# Ethernet.net
KiCad netlist of a schematic drawn in Altium Designer
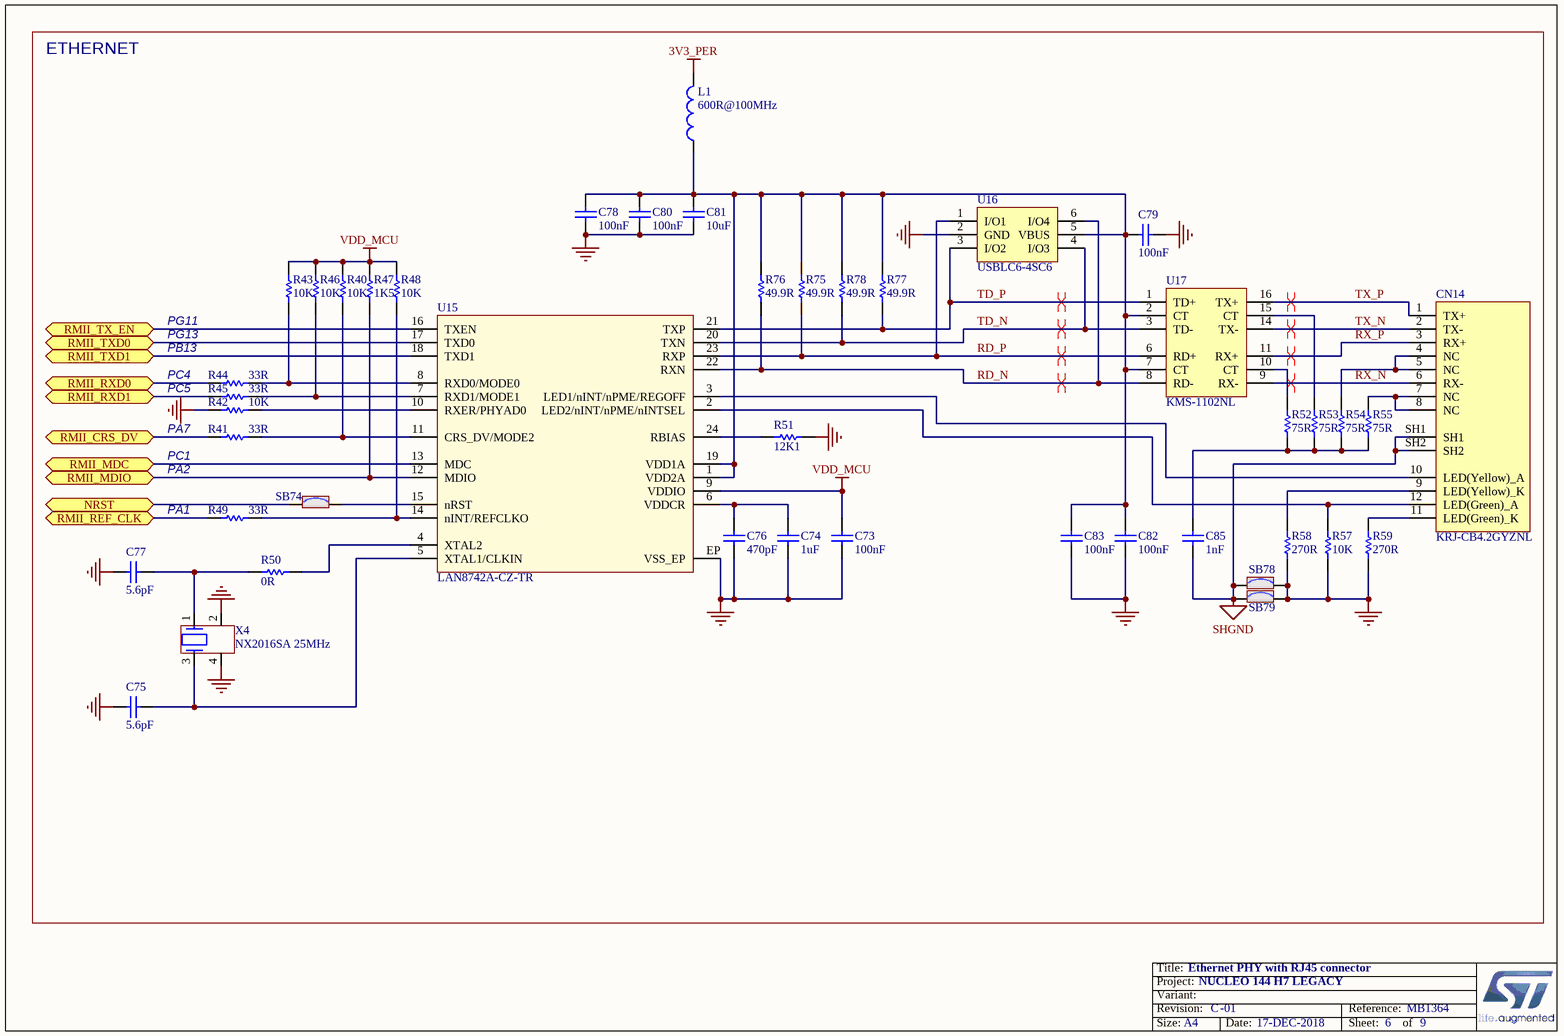
[diagram p0: Ethernet.SchDoc]

(export (version "E")
  (design (tool "Eeschema 10.0.6"))
  (components
    (comp (ref "C73")
      (value "100nF")
      (footprint "C0603")
      (description "Capacitor, MLCC, 100nF, 6V3, X5R, 10%, 0603, T=0,8mm")
      (fields
        (field (name "INTERNAL_PART_NUMBER") "MCD-00237")
        (field (name "MANUFACTURER_PART_NUMBER") "CC0603KRX5R5BB104")
        (field (name "PROVIDED_BY") "SUBCO")
      )
      (libsource (lib "MCD_PARTS_database") (part "Capacitor"))
    )
    (comp (ref "C74")
      (value "1uF")
      (footprint "C0402")
      (description "Capacitor, MLCC, 1uF, 6V3, X5R, 10%, 0402, T=0,5mm")
      (fields
        (field (name "INTERNAL_PART_NUMBER") "MCD-00095")
        (field (name "MANUFACTURER_PART_NUMBER") "GRM155R61E105KA12")
        (field (name "PROVIDED_BY") "SUBCO")
      )
      (libsource (lib "MCD_PARTS_database") (part "Capacitor"))
    )
    (comp (ref "C75")
      (value "5.6pF")
      (footprint "C0402")
      (description "Capacitor, MLCC, 5.6pF, 50V, NPO, 5%, 0402, T=0,5mm")
      (fields
        (field (name "INTERNAL_PART_NUMBER") "MCD-01374")
        (field (name "MANUFACTURER_PART_NUMBER") "CC0402BRNPO9BN5R6")
        (field (name "PROVIDED_BY") "SUBCO")
      )
      (libsource (lib "MCD_PARTS_database") (part "Capacitor"))
    )
    (comp (ref "C76")
      (value "470pF")
      (footprint "C0402")
      (description "Capacitor, MLCC, 470pF, 50V, NPO, 5%, 0402, T=0,5mm")
      (fields
        (field (name "INTERNAL_PART_NUMBER") "MCD-00724")
        (field (name "MANUFACTURER_PART_NUMBER") "CC0402JRNPO9BN471")
        (field (name "PROVIDED_BY") "SUBCO")
      )
      (libsource (lib "MCD_PARTS_database") (part "Capacitor"))
    )
    (comp (ref "C77")
      (value "5.6pF")
      (footprint "C0402")
      (description "Capacitor, MLCC, 5.6pF, 50V, NPO, 5%, 0402, T=0,5mm")
      (fields
        (field (name "INTERNAL_PART_NUMBER") "MCD-01374")
        (field (name "MANUFACTURER_PART_NUMBER") "CC0402BRNPO9BN5R6")
        (field (name "PROVIDED_BY") "SUBCO")
      )
      (libsource (lib "MCD_PARTS_database") (part "Capacitor"))
    )
    (comp (ref "C78")
      (value "100nF")
      (footprint "C0603")
      (description "Capacitor, MLCC, 100nF, 6V3, X5R, 10%, 0603, T=0,8mm")
      (fields
        (field (name "INTERNAL_PART_NUMBER") "MCD-00237")
        (field (name "MANUFACTURER_PART_NUMBER") "CC0603KRX5R5BB104")
        (field (name "PROVIDED_BY") "SUBCO")
      )
      (libsource (lib "MCD_PARTS_database") (part "Capacitor"))
    )
    (comp (ref "C79")
      (value "100nF")
      (footprint "C0603")
      (description "Capacitor, MLCC, 100nF, 6V3, X5R, 10%, 0603, T=0,8mm")
      (fields
        (field (name "INTERNAL_PART_NUMBER") "MCD-00237")
        (field (name "MANUFACTURER_PART_NUMBER") "CC0603KRX5R5BB104")
        (field (name "PROVIDED_BY") "SUBCO")
      )
      (libsource (lib "MCD_PARTS_database") (part "Capacitor"))
    )
    (comp (ref "C80")
      (value "100nF")
      (footprint "C0603")
      (description "Capacitor, MLCC, 100nF, 6V3, X5R, 10%, 0603, T=0,8mm")
      (fields
        (field (name "INTERNAL_PART_NUMBER") "MCD-00237")
        (field (name "MANUFACTURER_PART_NUMBER") "CC0603KRX5R5BB104")
        (field (name "PROVIDED_BY") "SUBCO")
      )
      (libsource (lib "MCD_PARTS_database") (part "Capacitor"))
    )
    (comp (ref "C81")
      (value "10uF")
      (footprint "C0603")
      (description "Capacitor, MLCC, 10µF, 10V, X5R, 10%, 0603, T=0.8mm")
      (fields
        (field (name "INTERNAL_PART_NUMBER") "MCD-01124")
        (field (name "MANUFACTURER_PART_NUMBER") "GRM188R61A106KAAL")
        (field (name "PROVIDED_BY") "SUBCO")
      )
      (libsource (lib "MCD_PARTS_database") (part "Capacitor"))
    )
    (comp (ref "C82")
      (value "100nF")
      (footprint "C0603")
      (description "Capacitor, MLCC, 100nF, 6V3, X5R, 10%, 0603, T=0,8mm")
      (fields
        (field (name "INTERNAL_PART_NUMBER") "MCD-00237")
        (field (name "MANUFACTURER_PART_NUMBER") "CC0603KRX5R5BB104")
        (field (name "PROVIDED_BY") "SUBCO")
      )
      (libsource (lib "MCD_PARTS_database") (part "Capacitor"))
    )
    (comp (ref "C83")
      (value "100nF")
      (footprint "C0603")
      (description "Capacitor, MLCC, 100nF, 6V3, X5R, 10%, 0603, T=0,8mm")
      (fields
        (field (name "INTERNAL_PART_NUMBER") "MCD-00237")
        (field (name "MANUFACTURER_PART_NUMBER") "CC0603KRX5R5BB104")
        (field (name "PROVIDED_BY") "SUBCO")
      )
      (libsource (lib "MCD_PARTS_database") (part "Capacitor"))
    )
    (comp (ref "C85")
      (value "1nF")
      (footprint "C1206_H1P6")
      (description "Capacitor, MLCC, 1nF, 2KV, X7R, 10%, 1206, T=1,25mm")
      (fields
        (field (name "INTERNAL_PART_NUMBER") "MCD-00722")
        (field (name "MANUFACTURER_PART_NUMBER") "CC1206KKX7RDBB102")
        (field (name "PROVIDED_BY") "SUBCO")
      )
      (libsource (lib "MCD_PARTS_database") (part "Capacitor"))
    )
    (comp (ref "CN14")
      (value "KRJ-CB4.2GYZNL")
      (footprint "CON_RJ45_DGKYD_KRJ-CB4.2GYZNL")
      (description "RJ45 jack, single port, with LEDS, Metal shielded dip low profile")
      (fields
        (field (name "INTERNAL_PART_NUMBER") "MCD-00717")
        (field (name "MANUFACTURER") "DONGGUAN KEYOUDA ELECTRONIC TECHNOLOGY")
        (field (name "PROVIDED_BY") "SUBCO")
      )
      (libsource (lib "MCD_PARTS_database") (part "RJ45_KRJ-CB4.2GYZNL"))
    )
    (comp (ref "L1")
      (value "600R@100MHz")
      (footprint "L0603")
      (description "SMD Chip ferrite bead, 600R@100MHz +/-25%, 350mA, 500mohm DC, 0603, T=0.8mm")
      (fields
        (field (name "INTERNAL_PART_NUMBER") "MCD-00047")
        (field (name "MANUFACTURER_PART_NUMBER") "FCM1608KF-601T03")
        (field (name "PROVIDED_BY") "SUBCO")
      )
      (libsource (lib "MCD_PARTS_database") (part "BEAD"))
    )
    (comp (ref "R40")
      (value "10K")
      (footprint "R0402")
      (description "Resistor,10K,0402,1%,1/16W")
      (fields
        (field (name "INTERNAL_PART_NUMBER") "MCD-00053")
        (field (name "MANUFACTURER_PART_NUMBER") "RC0402FR-0710KL")
        (field (name "PROVIDED_BY") "SUBCO")
      )
      (libsource (lib "MCD_PARTS_database") (part "Resistor"))
    )
    (comp (ref "R41")
      (value "33R")
      (footprint "R0402")
      (description "Resistor,33R,0402,1%,1/16W")
      (fields
        (field (name "INTERNAL_PART_NUMBER") "MCD-00455")
        (field (name "MANUFACTURER_PART_NUMBER") "RC0402FR-0733RL")
        (field (name "PROVIDED_BY") "SUBCO")
      )
      (libsource (lib "MCD_PARTS_database") (part "Resistor"))
    )
    (comp (ref "R42")
      (value "10K")
      (footprint "R0402")
      (description "Resistor,10K,0402,1%,1/16W")
      (fields
        (field (name "INTERNAL_PART_NUMBER") "MCD-00053")
        (field (name "MANUFACTURER_PART_NUMBER") "RC0402FR-0710KL")
        (field (name "PROVIDED_BY") "SUBCO")
      )
      (libsource (lib "MCD_PARTS_database") (part "Resistor"))
    )
    (comp (ref "R43")
      (value "10K")
      (footprint "R0402")
      (description "Resistor,10K,0402,1%,1/16W")
      (fields
        (field (name "INTERNAL_PART_NUMBER") "MCD-00053")
        (field (name "MANUFACTURER_PART_NUMBER") "RC0402FR-0710KL")
        (field (name "PROVIDED_BY") "SUBCO")
      )
      (libsource (lib "MCD_PARTS_database") (part "Resistor"))
    )
    (comp (ref "R44")
      (value "33R")
      (footprint "R0402")
      (description "Resistor,33R,0402,1%,1/16W")
      (fields
        (field (name "INTERNAL_PART_NUMBER") "MCD-00455")
        (field (name "MANUFACTURER_PART_NUMBER") "RC0402FR-0733RL")
        (field (name "PROVIDED_BY") "SUBCO")
      )
      (libsource (lib "MCD_PARTS_database") (part "Resistor"))
    )
    (comp (ref "R45")
      (value "33R")
      (footprint "R0402")
      (description "Resistor,33R,0402,1%,1/16W")
      (fields
        (field (name "INTERNAL_PART_NUMBER") "MCD-00455")
        (field (name "MANUFACTURER_PART_NUMBER") "RC0402FR-0733RL")
        (field (name "PROVIDED_BY") "SUBCO")
      )
      (libsource (lib "MCD_PARTS_database") (part "Resistor"))
    )
    (comp (ref "R46")
      (value "10K")
      (footprint "R0402")
      (description "Resistor,10K,0402,1%,1/16W")
      (fields
        (field (name "INTERNAL_PART_NUMBER") "MCD-00053")
        (field (name "MANUFACTURER_PART_NUMBER") "RC0402FR-0710KL")
        (field (name "PROVIDED_BY") "SUBCO")
      )
      (libsource (lib "MCD_PARTS_database") (part "Resistor"))
    )
    (comp (ref "R47")
      (value "1K5")
      (footprint "R0402")
      (description "Resistor,1K5,0402,1%,1/16W")
      (fields
        (field (name "INTERNAL_PART_NUMBER") "MCD-00068")
        (field (name "MANUFACTURER_PART_NUMBER") "RC0402FR-071K5L")
        (field (name "PROVIDED_BY") "SUBCO")
      )
      (libsource (lib "MCD_PARTS_database") (part "Resistor"))
    )
    (comp (ref "R48")
      (value "10K")
      (footprint "R0402")
      (description "Resistor,10K,0402,1%,1/16W")
      (fields
        (field (name "INTERNAL_PART_NUMBER") "MCD-00053")
        (field (name "MANUFACTURER_PART_NUMBER") "RC0402FR-0710KL")
        (field (name "PROVIDED_BY") "SUBCO")
      )
      (libsource (lib "MCD_PARTS_database") (part "Resistor"))
    )
    (comp (ref "R49")
      (value "33R")
      (footprint "R0402")
      (description "Resistor,33R,0402,1%,1/16W")
      (fields
        (field (name "INTERNAL_PART_NUMBER") "MCD-00455")
        (field (name "MANUFACTURER_PART_NUMBER") "RC0402FR-0733RL")
        (field (name "PROVIDED_BY") "SUBCO")
      )
      (libsource (lib "MCD_PARTS_database") (part "Resistor"))
    )
    (comp (ref "R50")
      (value "0R")
      (footprint "R0402")
      (description "Resistor,0R,0402,5%,1/16W")
      (fields
        (field (name "INTERNAL_PART_NUMBER") "MCD-00052")
        (field (name "MANUFACTURER_PART_NUMBER") "RC0402JR-070RL")
        (field (name "PROVIDED_BY") "SUBCO")
      )
      (libsource (lib "MCD_PARTS_database") (part "Resistor"))
    )
    (comp (ref "R51")
      (value "12K1")
      (footprint "R0402")
      (description "Resistor,12K1,0402,1%,1/16W")
      (fields
        (field (name "INTERNAL_PART_NUMBER") "MCD-00723")
        (field (name "MANUFACTURER_PART_NUMBER") "RC0402FR-0712K1L")
        (field (name "PROVIDED_BY") "SUBCO")
      )
      (libsource (lib "MCD_PARTS_database") (part "Resistor"))
    )
    (comp (ref "R52")
      (value "75R")
      (footprint "R0402")
      (description "Resistor,75R,0402,1%,1/16W")
      (fields
        (field (name "INTERNAL_PART_NUMBER") "MCD-00515")
        (field (name "MANUFACTURER_PART_NUMBER") "RC0402FR-0775RL")
        (field (name "PROVIDED_BY") "SUBCO")
      )
      (libsource (lib "MCD_PARTS_database") (part "Resistor"))
    )
    (comp (ref "R53")
      (value "75R")
      (footprint "R0402")
      (description "Resistor,75R,0402,1%,1/16W")
      (fields
        (field (name "INTERNAL_PART_NUMBER") "MCD-00515")
        (field (name "MANUFACTURER_PART_NUMBER") "RC0402FR-0775RL")
        (field (name "PROVIDED_BY") "SUBCO")
      )
      (libsource (lib "MCD_PARTS_database") (part "Resistor"))
    )
    (comp (ref "R54")
      (value "75R")
      (footprint "R0402")
      (description "Resistor,75R,0402,1%,1/16W")
      (fields
        (field (name "INTERNAL_PART_NUMBER") "MCD-00515")
        (field (name "MANUFACTURER_PART_NUMBER") "RC0402FR-0775RL")
        (field (name "PROVIDED_BY") "SUBCO")
      )
      (libsource (lib "MCD_PARTS_database") (part "Resistor"))
    )
    (comp (ref "R55")
      (value "75R")
      (footprint "R0402")
      (description "Resistor,75R,0402,1%,1/16W")
      (fields
        (field (name "INTERNAL_PART_NUMBER") "MCD-00515")
        (field (name "MANUFACTURER_PART_NUMBER") "RC0402FR-0775RL")
        (field (name "PROVIDED_BY") "SUBCO")
      )
      (libsource (lib "MCD_PARTS_database") (part "Resistor"))
    )
    (comp (ref "R57")
      (value "10K")
      (footprint "R0402")
      (description "Resistor,10K,0402,1%,1/16W")
      (fields
        (field (name "INTERNAL_PART_NUMBER") "MCD-00053")
        (field (name "MANUFACTURER_PART_NUMBER") "RC0402FR-0710KL")
        (field (name "PROVIDED_BY") "SUBCO")
      )
      (libsource (lib "MCD_PARTS_database") (part "Resistor"))
    )
    (comp (ref "R58")
      (value "270R")
      (footprint "R0402")
      (description "Resistor,270R,0402,1%,1/16W")
      (fields
        (field (name "INTERNAL_PART_NUMBER") "MCD-00441")
        (field (name "MANUFACTURER_PART_NUMBER") "RC0402FR-07270RL")
        (field (name "PROVIDED_BY") "SUBCO")
      )
      (libsource (lib "MCD_PARTS_database") (part "Resistor"))
    )
    (comp (ref "R59")
      (value "270R")
      (footprint "R0402")
      (description "Resistor,270R,0402,1%,1/16W")
      (fields
        (field (name "INTERNAL_PART_NUMBER") "MCD-00441")
        (field (name "MANUFACTURER_PART_NUMBER") "RC0402FR-07270RL")
        (field (name "PROVIDED_BY") "SUBCO")
      )
      (libsource (lib "MCD_PARTS_database") (part "Resistor"))
    )
    (comp (ref "R75")
      (value "49.9R")
      (footprint "R0402")
      (description "Resistor,49R9,0402,1%,1/16W")
      (fields
        (field (name "INTERNAL_PART_NUMBER") "MCD-00565")
        (field (name "MANUFACTURER_PART_NUMBER") "RC0402FR-0749R9L")
        (field (name "PROVIDED_BY") "SUBCO")
      )
      (libsource (lib "MCD_PARTS_database") (part "Resistor"))
    )
    (comp (ref "R76")
      (value "49.9R")
      (footprint "R0402")
      (description "Resistor,49R9,0402,1%,1/16W")
      (fields
        (field (name "INTERNAL_PART_NUMBER") "MCD-00565")
        (field (name "MANUFACTURER_PART_NUMBER") "RC0402FR-0749R9L")
        (field (name "PROVIDED_BY") "SUBCO")
      )
      (libsource (lib "MCD_PARTS_database") (part "Resistor"))
    )
    (comp (ref "R77")
      (value "49.9R")
      (footprint "R0402")
      (description "Resistor,49R9,0402,1%,1/16W")
      (fields
        (field (name "INTERNAL_PART_NUMBER") "MCD-00565")
        (field (name "MANUFACTURER_PART_NUMBER") "RC0402FR-0749R9L")
        (field (name "PROVIDED_BY") "SUBCO")
      )
      (libsource (lib "MCD_PARTS_database") (part "Resistor"))
    )
    (comp (ref "R78")
      (value "49.9R")
      (footprint "R0402")
      (description "Resistor,49R9,0402,1%,1/16W")
      (fields
        (field (name "INTERNAL_PART_NUMBER") "MCD-00565")
        (field (name "MANUFACTURER_PART_NUMBER") "RC0402FR-0749R9L")
        (field (name "PROVIDED_BY") "SUBCO")
      )
      (libsource (lib "MCD_PARTS_database") (part "Resistor"))
    )
    (comp (ref "SB74")
      (value "SB_ON")
      (footprint "SOLDER-BRIDGE_R0603-0R")
      (description "Solder Bridge ON")
      (fields
        (field (name "INTERNAL_PART_NUMBER") "MCD-00071")
        (field (name "MANUFACTURER_PART_NUMBER") "RC0603JR-070RL")
        (field (name "PROVIDED_BY") "SUBCO")
      )
      (libsource (lib "MCD_PARTS_database") (part "SB_ON"))
    )
    (comp (ref "SB78")
      (value "SB_ON")
      (footprint "SOLDER-BRIDGE_R0603-0R")
      (description "Solder Bridge ON")
      (fields
        (field (name "INTERNAL_PART_NUMBER") "MCD-00071")
        (field (name "MANUFACTURER_PART_NUMBER") "RC0603JR-070RL")
        (field (name "PROVIDED_BY") "SUBCO")
      )
      (libsource (lib "MCD_PARTS_database") (part "SB_ON"))
    )
    (comp (ref "SB79")
      (value "SB_ON")
      (footprint "SOLDER-BRIDGE_R0603-0R")
      (description "Solder Bridge ON")
      (fields
        (field (name "INTERNAL_PART_NUMBER") "MCD-00071")
        (field (name "MANUFACTURER_PART_NUMBER") "RC0603JR-070RL")
        (field (name "PROVIDED_BY") "SUBCO")
      )
      (libsource (lib "MCD_PARTS_database") (part "SB_ON"))
    )
    (comp (ref "U15")
      (value "LAN8742A-CZ-TR")
      (footprint "ICC_VQFN24-EPAD_4X4_P050")
      (description "10/100M RMII Ethernet transceiver")
      (fields
        (field (name "INTERNAL_PART_NUMBER") "MCD-00719")
        (field (name "MANUFACTURER") "MICROCHIP")
        (field (name "PROVIDED_BY") "SUBCO")
      )
      (libsource (lib "MCD_PARTS_database") (part "LAN8742A-CZ-TR"))
    )
    (comp (ref "U16")
      (value "USBLC6-4SC6")
      (footprint "ESD_SOT23-6L")
      (description "Very low capacitance ESD protection , 4 lines")
      (fields
        (field (name "INTERNAL_PART_NUMBER") "MCD-00250")
        (field (name "MANUFACTURER") "STMICROELECTRONICS")
        (field (name "PROVIDED_BY") "SUBCO with ST control")
      )
      (libsource (lib "MCD_PARTS_database") (part "USBLC6-4SC6"))
    )
    (comp (ref "U17")
      (value "KMS-1102NL")
      (footprint "TRS_DGKYD_KMS-1102NL")
      (description "Discrete Magnetic Transformer Module, 16 pins, SMT, 100 Base-TX")
      (fields
        (field (name "INTERNAL_PART_NUMBER") "MCD-00718")
        (field (name "MANUFACTURER") "DONGGUAN KEYOUDA ELECTRONIC TECHNOLOGY")
        (field (name "PROVIDED_BY") "SUBCO")
      )
      (libsource (lib "MCD_PARTS_database") (part "KMS-1102NL"))
    )
    (comp (ref "X4")
      (value "NX2016SA 25MHz")
      (footprint "CRY_NX2016SA_4P")
      (description "Crystal 25MHz, 6pF, +-20ppm, 80ohms max, SMD")
      (fields
        (field (name "INTERNAL_PART_NUMBER") "MCD-01364")
        (field (name "MANUFACTURER_PART_NUMBER") "NX2016SA 25MHz EXS00A-CS11321")
        (field (name "PROVIDED_BY") "SUBCO")
      )
      (libsource (lib "MCD_PARTS_database") (part "XTAL_4_PINS"))
    )
  )
  (nets
    (net (code "1") (name "/NRST") (class "Default")
      (node (ref "SB74") (pin "1") (pinfunction "1_1") (pintype "passive"))
    )
    (net (code "2") (name "/RD_N") (class "Default")
      (node (ref "R76") (pin "1") (pinfunction "1_1") (pintype "passive"))
      (node (ref "U15") (pin "22") (pinfunction "RXN_22") (pintype "passive"))
      (node (ref "U16") (pin "6") (pinfunction "I/O4_6") (pintype "passive"))
      (node (ref "U17") (pin "8") (pinfunction "RD-_8") (pintype "passive"))
    )
    (net (code "3") (name "/RD_P") (class "Default")
      (node (ref "R75") (pin "1") (pinfunction "1_1") (pintype "passive"))
      (node (ref "U15") (pin "23") (pinfunction "RXP_23") (pintype "passive"))
      (node (ref "U16") (pin "1") (pinfunction "I/O1_1") (pintype "passive"))
      (node (ref "U17") (pin "6") (pinfunction "RD+_6") (pintype "passive"))
    )
    (net (code "4") (name "/RMII_CRS_DV") (class "Default")
      (node (ref "R41") (pin "1") (pinfunction "1_1") (pintype "passive"))
    )
    (net (code "5") (name "/RMII_MDC") (class "Default")
      (node (ref "U15") (pin "13") (pinfunction "MDC_13") (pintype "passive"))
    )
    (net (code "6") (name "/RMII_MDIO") (class "Default")
      (node (ref "R47") (pin "1") (pinfunction "1_1") (pintype "passive"))
      (node (ref "U15") (pin "12") (pinfunction "MDIO_12") (pintype "passive"))
    )
    (net (code "7") (name "/RMII_REF_CLK") (class "Default")
      (node (ref "R49") (pin "1") (pinfunction "1_1") (pintype "passive"))
    )
    (net (code "8") (name "/RMII_RXD0") (class "Default")
      (node (ref "R44") (pin "1") (pinfunction "1_1") (pintype "passive"))
    )
    (net (code "9") (name "/RMII_RXD1") (class "Default")
      (node (ref "R45") (pin "1") (pinfunction "1_1") (pintype "passive"))
    )
    (net (code "10") (name "/RMII_TXD0") (class "Default")
      (node (ref "U15") (pin "17") (pinfunction "TXD0_17") (pintype "passive"))
    )
    (net (code "11") (name "/RMII_TXD1") (class "Default")
      (node (ref "U15") (pin "18") (pinfunction "TXD1_18") (pintype "passive"))
    )
    (net (code "12") (name "/RMII_TX_EN") (class "Default")
      (node (ref "U15") (pin "16") (pinfunction "TXEN_16") (pintype "passive"))
    )
    (net (code "13") (name "/RX_N") (class "Default")
      (node (ref "CN14") (pin "6") (pinfunction "RX-_6") (pintype "passive"))
      (node (ref "U17") (pin "9") (pinfunction "RX-_9") (pintype "passive"))
    )
    (net (code "14") (name "/RX_P") (class "Default")
      (node (ref "CN14") (pin "3") (pinfunction "RX+_3") (pintype "passive"))
      (node (ref "U17") (pin "11") (pinfunction "RX+_11") (pintype "passive"))
    )
    (net (code "15") (name "/TD_N") (class "Default")
      (node (ref "R78") (pin "1") (pinfunction "1_1") (pintype "passive"))
      (node (ref "U15") (pin "20") (pinfunction "TXN_20") (pintype "passive"))
      (node (ref "U16") (pin "4") (pinfunction "I/O3_4") (pintype "passive"))
      (node (ref "U17") (pin "3") (pinfunction "TD-_3") (pintype "passive"))
    )
    (net (code "16") (name "/TD_P") (class "Default")
      (node (ref "R77") (pin "1") (pinfunction "1_1") (pintype "passive"))
      (node (ref "U15") (pin "21") (pinfunction "TXP_21") (pintype "passive"))
      (node (ref "U16") (pin "3") (pinfunction "I/O2_3") (pintype "passive"))
      (node (ref "U17") (pin "1") (pinfunction "TD+_1") (pintype "passive"))
    )
    (net (code "17") (name "/TX_N") (class "Default")
      (node (ref "CN14") (pin "2") (pinfunction "TX-_2") (pintype "passive"))
      (node (ref "U17") (pin "14") (pinfunction "TX-_14") (pintype "passive"))
    )
    (net (code "18") (name "/TX_P") (class "Default")
      (node (ref "CN14") (pin "1") (pinfunction "TX+_1") (pintype "passive"))
      (node (ref "U17") (pin "16") (pinfunction "TX+_16") (pintype "passive"))
    )
    (net (code "19") (name "3V3_PER") (class "Default")
      (node (ref "L1") (pin "2") (pinfunction "2_2") (pintype "passive"))
    )
    (net (code "20") (name "GND") (class "Default")
      (node (ref "C73") (pin "1") (pinfunction "1_1") (pintype "passive"))
      (node (ref "C74") (pin "1") (pinfunction "1_1") (pintype "passive"))
      (node (ref "C75") (pin "1") (pinfunction "1_1") (pintype "passive"))
      (node (ref "C76") (pin "1") (pinfunction "1_1") (pintype "passive"))
      (node (ref "C77") (pin "1") (pinfunction "1_1") (pintype "passive"))
      (node (ref "C78") (pin "1") (pinfunction "1_1") (pintype "passive"))
      (node (ref "C79") (pin "2") (pinfunction "2_2") (pintype "passive"))
      (node (ref "C80") (pin "1") (pinfunction "1_1") (pintype "passive"))
      (node (ref "C81") (pin "1") (pinfunction "1_1") (pintype "passive"))
      (node (ref "C82") (pin "1") (pinfunction "1_1") (pintype "passive"))
      (node (ref "C83") (pin "1") (pinfunction "1_1") (pintype "passive"))
      (node (ref "R42") (pin "2") (pinfunction "2_2") (pintype "passive"))
      (node (ref "R51") (pin "2") (pinfunction "2_2") (pintype "passive"))
      (node (ref "R57") (pin "1") (pinfunction "1_1") (pintype "passive"))
      (node (ref "R58") (pin "1") (pinfunction "1_1") (pintype "passive"))
      (node (ref "R59") (pin "1") (pinfunction "1_1") (pintype "passive"))
      (node (ref "SB78") (pin "2") (pinfunction "2_2") (pintype "passive"))
      (node (ref "SB79") (pin "2") (pinfunction "2_2") (pintype "passive"))
      (node (ref "U15") (pin "EP") (pinfunction "VSS_EP_EP") (pintype "passive"))
      (node (ref "U16") (pin "2") (pinfunction "GND_2") (pintype "passive"))
      (node (ref "X4") (pin "2") (pinfunction "2_2") (pintype "passive"))
      (node (ref "X4") (pin "4") (pinfunction "4_4") (pintype "passive"))
    )
    (net (code "21") (name "Net-(C77-Pad2)") (class "Default")
      (node (ref "C77") (pin "2") (pinfunction "2_2") (pintype "passive"))
      (node (ref "R50") (pin "1") (pinfunction "1_1") (pintype "passive"))
      (node (ref "X4") (pin "1") (pinfunction "1_1") (pintype "passive"))
    )
    (net (code "22") (name "Net-(C85-Pad2)") (class "Default")
      (node (ref "C85") (pin "2") (pinfunction "2_2") (pintype "passive"))
      (node (ref "R52") (pin "1") (pinfunction "1_1") (pintype "passive"))
      (node (ref "R53") (pin "1") (pinfunction "1_1") (pintype "passive"))
      (node (ref "R54") (pin "1") (pinfunction "1_1") (pintype "passive"))
      (node (ref "R55") (pin "1") (pinfunction "1_1") (pintype "passive"))
    )
    (net (code "23") (name "Net-(CN14-LED(Green)_A)") (class "Default")
      (node (ref "CN14") (pin "12") (pinfunction "LED(Green)_A_12") (pintype "passive"))
      (node (ref "R57") (pin "2") (pinfunction "2_2") (pintype "passive"))
      (node (ref "U15") (pin "2") (pinfunction "LED2/nINT/nPME/nINTSEL_2") (pintype "passive"))
    )
    (net (code "24") (name "Net-(CN14-LED(Green)_K)") (class "Default")
      (node (ref "CN14") (pin "11") (pinfunction "LED(Green)_K_11") (pintype "passive"))
      (node (ref "R59") (pin "2") (pinfunction "2_2") (pintype "passive"))
    )
    (net (code "25") (name "Net-(CN14-LED(Yellow)_A)") (class "Default")
      (node (ref "CN14") (pin "10") (pinfunction "LED(Yellow)_A_10") (pintype "passive"))
      (node (ref "U15") (pin "3") (pinfunction "LED1/nINT/nPME/REGOFF_3") (pintype "passive"))
    )
    (net (code "26") (name "Net-(CN14-LED(Yellow)_K)") (class "Default")
      (node (ref "CN14") (pin "9") (pinfunction "LED(Yellow)_K_9") (pintype "passive"))
      (node (ref "R58") (pin "2") (pinfunction "2_2") (pintype "passive"))
    )
    (net (code "27") (name "Net-(CN14-NC-Pad4)") (class "Default")
      (node (ref "CN14") (pin "4") (pinfunction "NC_4") (pintype "passive"))
      (node (ref "CN14") (pin "5") (pinfunction "NC_5") (pintype "passive"))
      (node (ref "R54") (pin "2") (pinfunction "2_2") (pintype "passive"))
    )
    (net (code "28") (name "Net-(CN14-NC-Pad7)") (class "Default")
      (node (ref "CN14") (pin "7") (pinfunction "NC_7") (pintype "passive"))
      (node (ref "CN14") (pin "8") (pinfunction "NC_8") (pintype "passive"))
      (node (ref "R55") (pin "2") (pinfunction "2_2") (pintype "passive"))
    )
    (net (code "29") (name "Net-(R52-Pad2)") (class "Default")
      (node (ref "R52") (pin "2") (pinfunction "2_2") (pintype "passive"))
      (node (ref "U17") (pin "10") (pinfunction "CT_10") (pintype "passive"))
    )
    (net (code "30") (name "Net-(R53-Pad2)") (class "Default")
      (node (ref "R53") (pin "2") (pinfunction "2_2") (pintype "passive"))
      (node (ref "U17") (pin "15") (pinfunction "CT_15") (pintype "passive"))
    )
    (net (code "31") (name "Net-(U15-CRS_DV{slash}MODE2)") (class "Default")
      (node (ref "R40") (pin "1") (pinfunction "1_1") (pintype "passive"))
      (node (ref "R41") (pin "2") (pinfunction "2_2") (pintype "passive"))
      (node (ref "U15") (pin "11") (pinfunction "CRS_DV/MODE2_11") (pintype "passive"))
    )
    (net (code "32") (name "Net-(U15-RBIAS)") (class "Default")
      (node (ref "R51") (pin "1") (pinfunction "1_1") (pintype "passive"))
      (node (ref "U15") (pin "24") (pinfunction "RBIAS_24") (pintype "passive"))
    )
    (net (code "33") (name "Net-(U15-RXD0{slash}MODE0)") (class "Default")
      (node (ref "R43") (pin "1") (pinfunction "1_1") (pintype "passive"))
      (node (ref "R44") (pin "2") (pinfunction "2_2") (pintype "passive"))
      (node (ref "U15") (pin "8") (pinfunction "RXD0/MODE0_8") (pintype "passive"))
    )
    (net (code "34") (name "Net-(U15-RXD1{slash}MODE1)") (class "Default")
      (node (ref "R45") (pin "2") (pinfunction "2_2") (pintype "passive"))
      (node (ref "R46") (pin "1") (pinfunction "1_1") (pintype "passive"))
      (node (ref "U15") (pin "7") (pinfunction "RXD1/MODE1_7") (pintype "passive"))
    )
    (net (code "35") (name "Net-(U15-RXER{slash}PHYAD0)") (class "Default")
      (node (ref "R42") (pin "1") (pinfunction "1_1") (pintype "passive"))
      (node (ref "U15") (pin "10") (pinfunction "RXER/PHYAD0_10") (pintype "passive"))
    )
    (net (code "36") (name "Net-(U15-VDD1A)") (class "Default")
      (node (ref "C78") (pin "2") (pinfunction "2_2") (pintype "passive"))
      (node (ref "C79") (pin "1") (pinfunction "1_1") (pintype "passive"))
      (node (ref "C80") (pin "2") (pinfunction "2_2") (pintype "passive"))
      (node (ref "C81") (pin "2") (pinfunction "2_2") (pintype "passive"))
      (node (ref "C82") (pin "2") (pinfunction "2_2") (pintype "passive"))
      (node (ref "C83") (pin "2") (pinfunction "2_2") (pintype "passive"))
      (node (ref "L1") (pin "1") (pinfunction "1_1") (pintype "passive"))
      (node (ref "R75") (pin "2") (pinfunction "2_2") (pintype "passive"))
      (node (ref "R76") (pin "2") (pinfunction "2_2") (pintype "passive"))
      (node (ref "R77") (pin "2") (pinfunction "2_2") (pintype "passive"))
      (node (ref "R78") (pin "2") (pinfunction "2_2") (pintype "passive"))
      (node (ref "U15") (pin "1") (pinfunction "VDD2A_1") (pintype "passive"))
      (node (ref "U15") (pin "19") (pinfunction "VDD1A_19") (pintype "passive"))
      (node (ref "U16") (pin "5") (pinfunction "VBUS_5") (pintype "passive"))
      (node (ref "U17") (pin "2") (pinfunction "CT_2") (pintype "passive"))
      (node (ref "U17") (pin "7") (pinfunction "CT_7") (pintype "passive"))
    )
    (net (code "37") (name "Net-(U15-VDDCR)") (class "Default")
      (node (ref "C74") (pin "2") (pinfunction "2_2") (pintype "passive"))
      (node (ref "C76") (pin "2") (pinfunction "2_2") (pintype "passive"))
      (node (ref "U15") (pin "6") (pinfunction "VDDCR_6") (pintype "passive"))
    )
    (net (code "38") (name "Net-(U15-XTAL1{slash}CLKIN)") (class "Default")
      (node (ref "C75") (pin "2") (pinfunction "2_2") (pintype "passive"))
      (node (ref "U15") (pin "5") (pinfunction "XTAL1/CLKIN_5") (pintype "passive"))
      (node (ref "X4") (pin "3") (pinfunction "3_3") (pintype "passive"))
    )
    (net (code "39") (name "Net-(U15-XTAL2)") (class "Default")
      (node (ref "R50") (pin "2") (pinfunction "2_2") (pintype "passive"))
      (node (ref "U15") (pin "4") (pinfunction "XTAL2_4") (pintype "passive"))
    )
    (net (code "40") (name "Net-(U15-nINT{slash}REFCLKO)") (class "Default")
      (node (ref "R48") (pin "1") (pinfunction "1_1") (pintype "passive"))
      (node (ref "R49") (pin "2") (pinfunction "2_2") (pintype "passive"))
      (node (ref "U15") (pin "14") (pinfunction "nINT/REFCLKO_14") (pintype "passive"))
    )
    (net (code "41") (name "Net-(U15-nRST)") (class "Default")
      (node (ref "SB74") (pin "2") (pinfunction "2_2") (pintype "passive"))
      (node (ref "U15") (pin "15") (pinfunction "nRST_15") (pintype "passive"))
    )
    (net (code "42") (name "SHGND") (class "Default")
      (node (ref "C85") (pin "1") (pinfunction "1_1") (pintype "passive"))
      (node (ref "CN14") (pin "SH1") (pinfunction "SH1_SH1") (pintype "passive"))
      (node (ref "CN14") (pin "SH2") (pinfunction "SH2_SH2") (pintype "passive"))
      (node (ref "SB78") (pin "1") (pinfunction "1_1") (pintype "passive"))
      (node (ref "SB79") (pin "1") (pinfunction "1_1") (pintype "passive"))
    )
    (net (code "43") (name "VDD_MCU") (class "Default")
      (node (ref "C73") (pin "2") (pinfunction "2_2") (pintype "passive"))
      (node (ref "R40") (pin "2") (pinfunction "2_2") (pintype "passive"))
      (node (ref "R43") (pin "2") (pinfunction "2_2") (pintype "passive"))
      (node (ref "R46") (pin "2") (pinfunction "2_2") (pintype "passive"))
      (node (ref "R47") (pin "2") (pinfunction "2_2") (pintype "passive"))
      (node (ref "R48") (pin "2") (pinfunction "2_2") (pintype "passive"))
      (node (ref "U15") (pin "9") (pinfunction "VDDIO_9") (pintype "passive"))
    )
  )
)
